# SCH_Hand_2024-01-24.net
KiCad netlist of a schematic drawn in EasyEDA
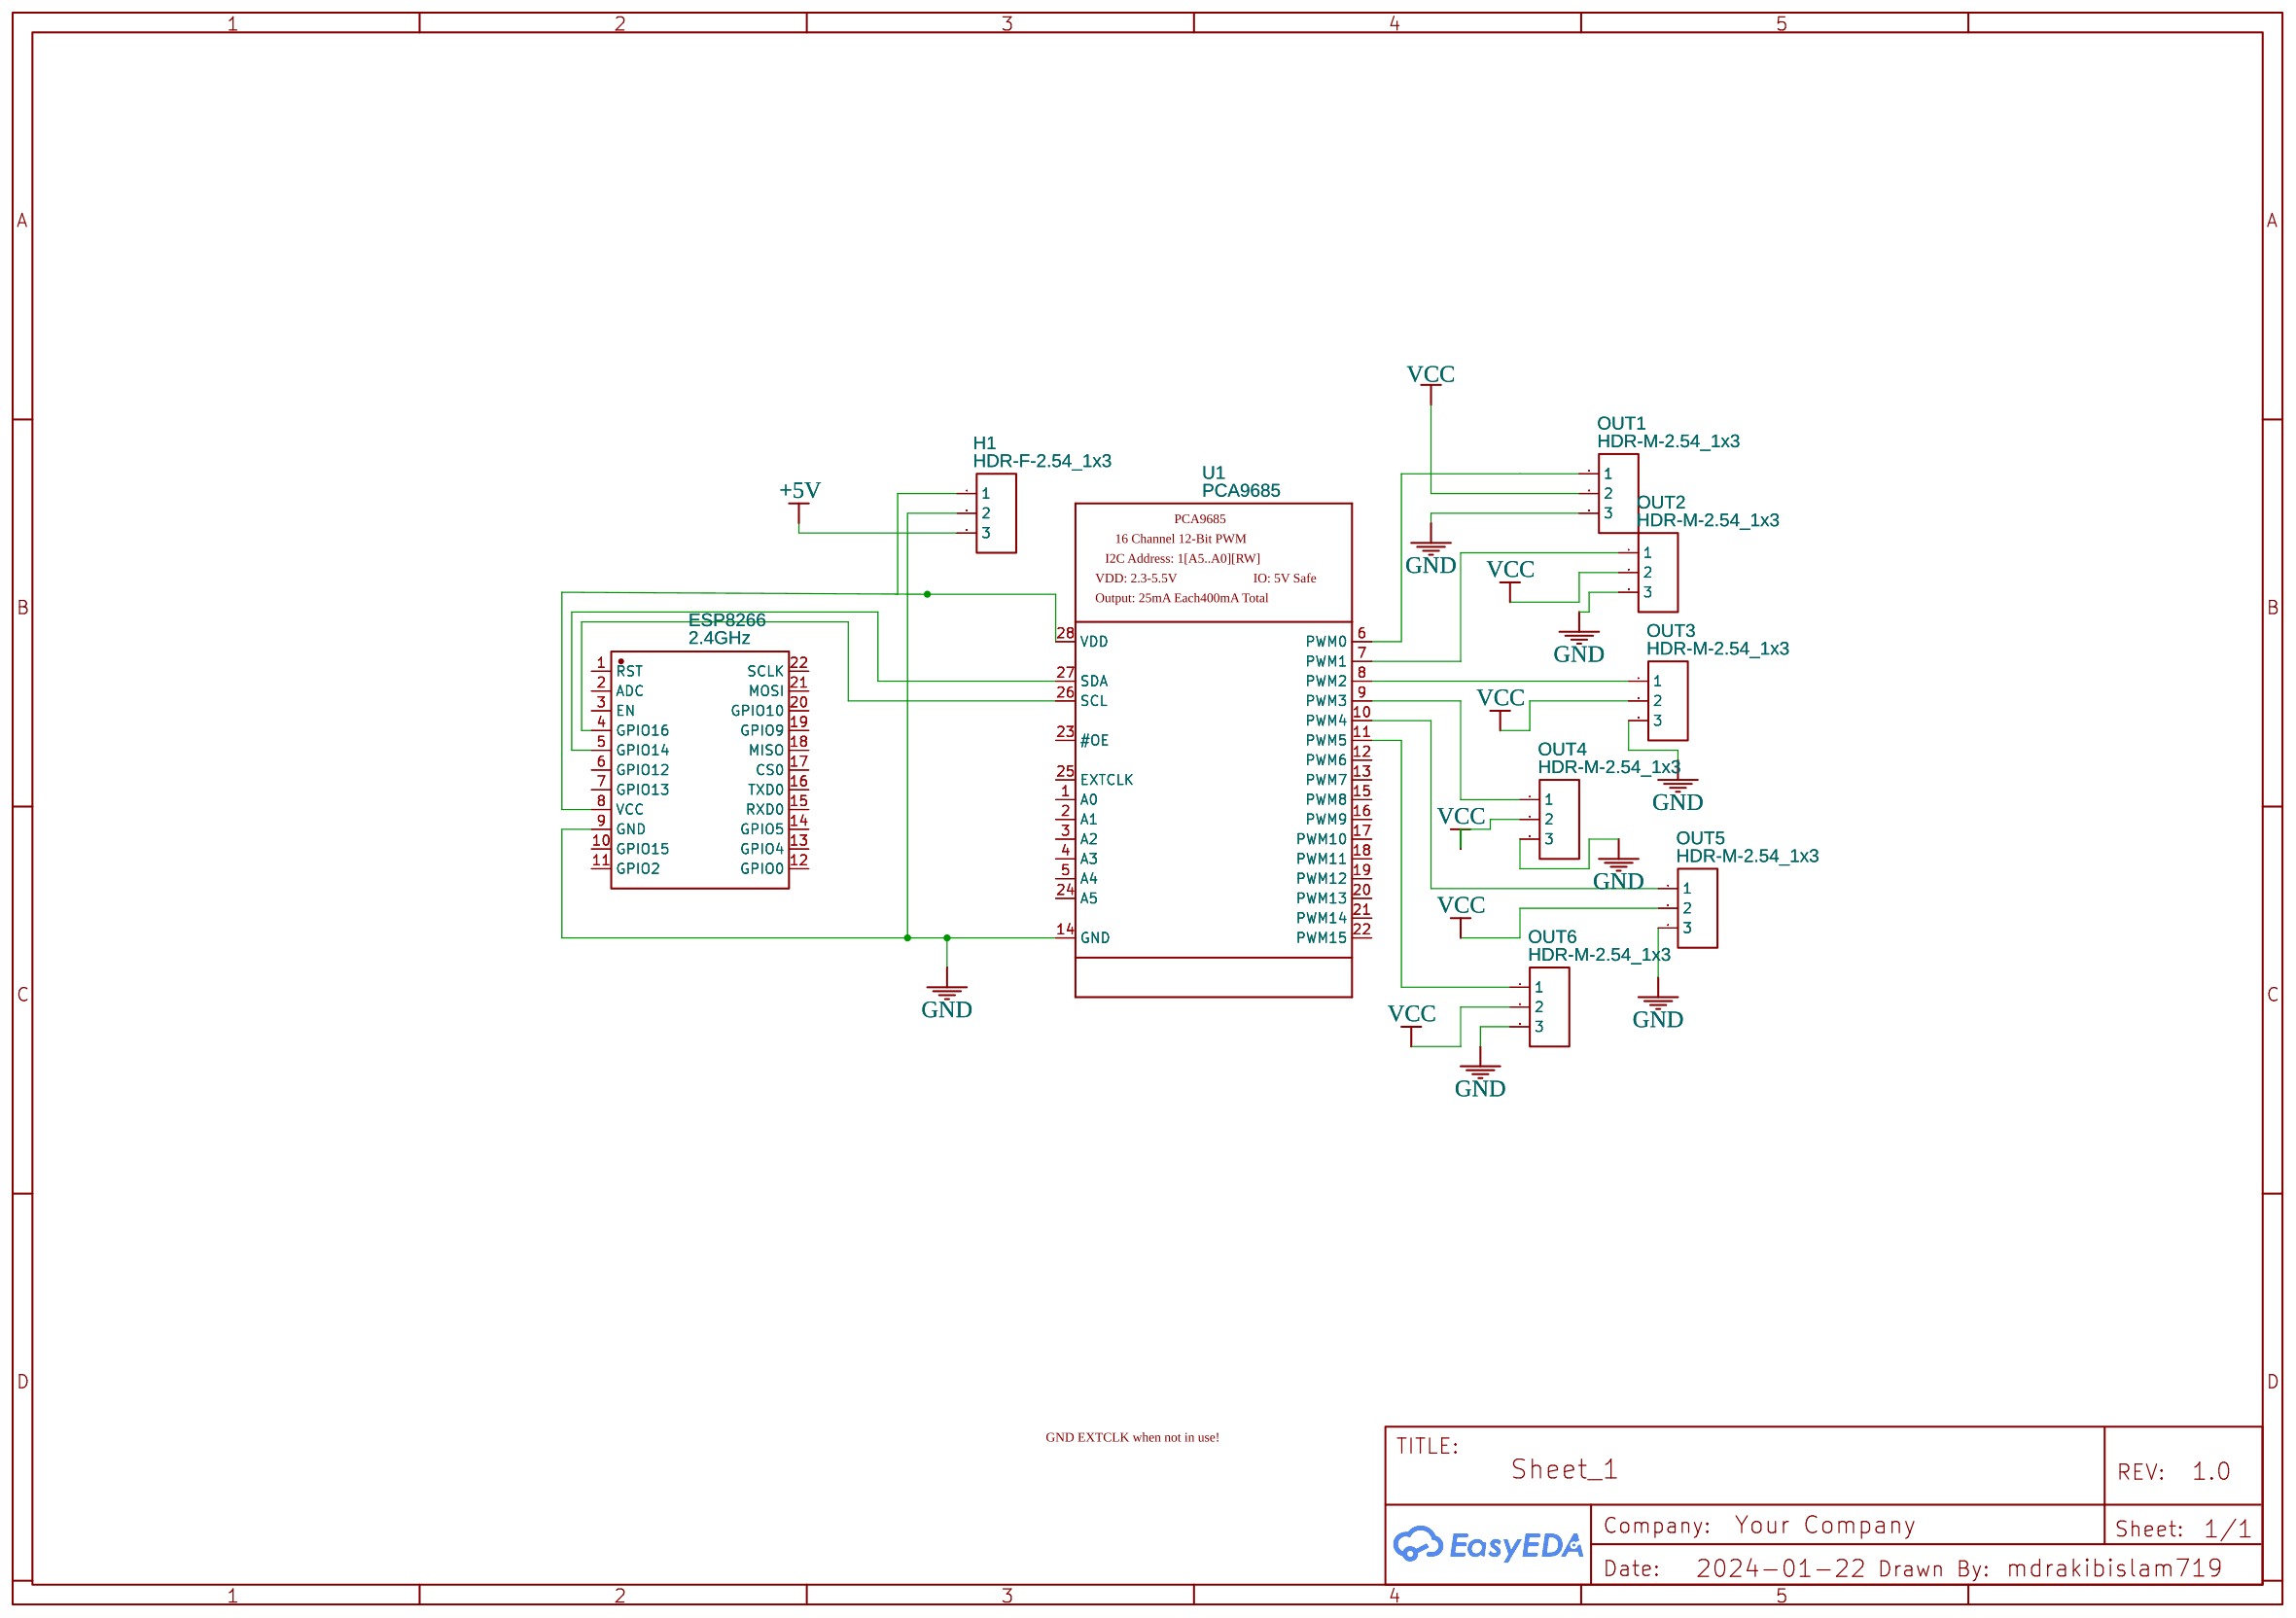
[diagram p0: schematic sheet]

(export (version "E")
  (design (tool "Eeschema 10.0.6"))
  (components
    (comp (ref "ESP8266")
      (value "2.4GHz")
      (fields
        (field (name "Manufacturer Part") "ESP-12F(ESP8266MOD)")
        (field (name "Manufacturer") "Ai-Thinker(安信可)")
      )
      (libsource (lib "") (part "ESP-12F(ESP8266MOD)"))
    )
    (comp (ref "H1") (value "HDR-F-2.54_1x3") (libsource (lib "") (part "HDR-F-2.54_1x3")))
    (comp (ref "OUT1") (value "HDR-M-2.54_1x3") (libsource (lib "") (part "HDR-M-2.54_1x3")))
    (comp (ref "OUT2") (value "HDR-M-2.54_1x3") (libsource (lib "") (part "HDR-M-2.54_1x3")))
    (comp (ref "OUT3") (value "HDR-M-2.54_1x3") (libsource (lib "") (part "HDR-M-2.54_1x3")))
    (comp (ref "OUT4") (value "HDR-M-2.54_1x3") (libsource (lib "") (part "HDR-M-2.54_1x3")))
    (comp (ref "OUT5") (value "HDR-M-2.54_1x3") (libsource (lib "") (part "HDR-M-2.54_1x3")))
    (comp (ref "OUT6") (value "HDR-M-2.54_1x3") (libsource (lib "") (part "HDR-M-2.54_1x3")))
    (comp (ref "U1") (value "PCA9685") (libsource (lib "") (part "PCA9685")))
  )
  (nets
    (net (code "1") (name "+5V") (class "Default")
      (node (ref "H1") (pin "3") (pinfunction "3_3") (pintype "input"))
    )
    (net (code "2") (name "GND") (class "Default")
      (node (ref "ESP8266") (pin "9") (pinfunction "GND_9") (pintype "unspecified"))
      (node (ref "H1") (pin "2") (pinfunction "2_2") (pintype "input"))
      (node (ref "OUT1") (pin "3") (pinfunction "3_3") (pintype "input"))
      (node (ref "OUT2") (pin "3") (pinfunction "3_3") (pintype "input"))
      (node (ref "OUT3") (pin "3") (pinfunction "3_3") (pintype "input"))
      (node (ref "OUT4") (pin "3") (pinfunction "3_3") (pintype "input"))
      (node (ref "OUT5") (pin "3") (pinfunction "3_3") (pintype "input"))
      (node (ref "OUT6") (pin "3") (pinfunction "3_3") (pintype "input"))
      (node (ref "U1") (pin "14") (pinfunction "GND_14") (pintype "passive"))
    )
    (net (code "3") (name "Net-(ESP8266-GPIO14)") (class "Default")
      (node (ref "ESP8266") (pin "5") (pinfunction "GPIO14_5") (pintype "unspecified"))
      (node (ref "U1") (pin "27") (pinfunction "SDA_27") (pintype "unspecified"))
    )
    (net (code "4") (name "Net-(ESP8266-GPIO16)") (class "Default")
      (node (ref "ESP8266") (pin "4") (pinfunction "GPIO16_4") (pintype "unspecified"))
      (node (ref "U1") (pin "26") (pinfunction "SCL_26") (pintype "unspecified"))
    )
    (net (code "5") (name "Net-(ESP8266-VCC)") (class "Default")
      (node (ref "ESP8266") (pin "8") (pinfunction "VCC_8") (pintype "unspecified"))
      (node (ref "U1") (pin "28") (pinfunction "VDD_28") (pintype "passive"))
    )
    (net (code "6") (name "Net-(U1-PWM0)") (class "Default")
      (node (ref "OUT1") (pin "1") (pinfunction "1_1") (pintype "input"))
      (node (ref "U1") (pin "6") (pinfunction "PWM0_6") (pintype "output"))
    )
    (net (code "7") (name "Net-(U1-PWM1)") (class "Default")
      (node (ref "OUT2") (pin "1") (pinfunction "1_1") (pintype "input"))
      (node (ref "U1") (pin "7") (pinfunction "PWM1_7") (pintype "output"))
    )
    (net (code "8") (name "Net-(U1-PWM2)") (class "Default")
      (node (ref "OUT3") (pin "1") (pinfunction "1_1") (pintype "input"))
      (node (ref "U1") (pin "8") (pinfunction "PWM2_8") (pintype "output"))
    )
    (net (code "9") (name "Net-(U1-PWM3)") (class "Default")
      (node (ref "OUT4") (pin "1") (pinfunction "1_1") (pintype "input"))
      (node (ref "U1") (pin "9") (pinfunction "PWM3_9") (pintype "output"))
    )
    (net (code "10") (name "Net-(U1-PWM4)") (class "Default")
      (node (ref "OUT5") (pin "1") (pinfunction "1_1") (pintype "input"))
      (node (ref "U1") (pin "10") (pinfunction "PWM4_10") (pintype "output"))
    )
    (net (code "11") (name "Net-(U1-PWM5)") (class "Default")
      (node (ref "OUT6") (pin "1") (pinfunction "1_1") (pintype "input"))
      (node (ref "U1") (pin "11") (pinfunction "PWM5_11") (pintype "output"))
    )
    (net (code "12") (name "VCC") (class "Default")
      (node (ref "OUT1") (pin "2") (pinfunction "2_2") (pintype "input"))
      (node (ref "OUT2") (pin "2") (pinfunction "2_2") (pintype "input"))
      (node (ref "OUT3") (pin "2") (pinfunction "2_2") (pintype "input"))
      (node (ref "OUT4") (pin "2") (pinfunction "2_2") (pintype "input"))
      (node (ref "OUT5") (pin "2") (pinfunction "2_2") (pintype "input"))
      (node (ref "OUT6") (pin "2") (pinfunction "2_2") (pintype "input"))
    )
    (net (code "13") (name "unconnected-(ESP8266-ADC-Pad2)") (class "Default")
      (node (ref "ESP8266") (pin "2") (pinfunction "ADC_2") (pintype "unspecified"))
    )
    (net (code "14") (name "unconnected-(ESP8266-CS0-Pad17)") (class "Default")
      (node (ref "ESP8266") (pin "17") (pinfunction "CS0_17") (pintype "unspecified"))
    )
    (net (code "15") (name "unconnected-(ESP8266-EN-Pad3)") (class "Default")
      (node (ref "ESP8266") (pin "3") (pinfunction "EN_3") (pintype "unspecified"))
    )
    (net (code "16") (name "unconnected-(ESP8266-GPIO0-Pad12)") (class "Default")
      (node (ref "ESP8266") (pin "12") (pinfunction "GPIO0_12") (pintype "unspecified"))
    )
    (net (code "17") (name "unconnected-(ESP8266-GPIO2-Pad11)") (class "Default")
      (node (ref "ESP8266") (pin "11") (pinfunction "GPIO2_11") (pintype "unspecified"))
    )
    (net (code "18") (name "unconnected-(ESP8266-GPIO4-Pad13)") (class "Default")
      (node (ref "ESP8266") (pin "13") (pinfunction "GPIO4_13") (pintype "unspecified"))
    )
    (net (code "19") (name "unconnected-(ESP8266-GPIO5-Pad14)") (class "Default")
      (node (ref "ESP8266") (pin "14") (pinfunction "GPIO5_14") (pintype "unspecified"))
    )
    (net (code "20") (name "unconnected-(ESP8266-GPIO9-Pad19)") (class "Default")
      (node (ref "ESP8266") (pin "19") (pinfunction "GPIO9_19") (pintype "unspecified"))
    )
    (net (code "21") (name "unconnected-(ESP8266-GPIO10-Pad20)") (class "Default")
      (node (ref "ESP8266") (pin "20") (pinfunction "GPIO10_20") (pintype "unspecified"))
    )
    (net (code "22") (name "unconnected-(ESP8266-GPIO12-Pad6)") (class "Default")
      (node (ref "ESP8266") (pin "6") (pinfunction "GPIO12_6") (pintype "unspecified"))
    )
    (net (code "23") (name "unconnected-(ESP8266-GPIO13-Pad7)") (class "Default")
      (node (ref "ESP8266") (pin "7") (pinfunction "GPIO13_7") (pintype "unspecified"))
    )
    (net (code "24") (name "unconnected-(ESP8266-GPIO15-Pad10)") (class "Default")
      (node (ref "ESP8266") (pin "10") (pinfunction "GPIO15_10") (pintype "unspecified"))
    )
    (net (code "25") (name "unconnected-(ESP8266-MISO-Pad18)") (class "Default")
      (node (ref "ESP8266") (pin "18") (pinfunction "MISO_18") (pintype "unspecified"))
    )
    (net (code "26") (name "unconnected-(ESP8266-MOSI-Pad21)") (class "Default")
      (node (ref "ESP8266") (pin "21") (pinfunction "MOSI_21") (pintype "unspecified"))
    )
    (net (code "27") (name "unconnected-(ESP8266-RST-Pad1)") (class "Default")
      (node (ref "ESP8266") (pin "1") (pinfunction "RST_1") (pintype "unspecified"))
    )
    (net (code "28") (name "unconnected-(ESP8266-RXD0-Pad15)") (class "Default")
      (node (ref "ESP8266") (pin "15") (pinfunction "RXD0_15") (pintype "unspecified"))
    )
    (net (code "29") (name "unconnected-(ESP8266-SCLK-Pad22)") (class "Default")
      (node (ref "ESP8266") (pin "22") (pinfunction "SCLK_22") (pintype "unspecified"))
    )
    (net (code "30") (name "unconnected-(ESP8266-TXD0-Pad16)") (class "Default")
      (node (ref "ESP8266") (pin "16") (pinfunction "TXD0_16") (pintype "unspecified"))
    )
    (net (code "31") (name "unconnected-(H1-Pad1)") (class "Default")
      (node (ref "H1") (pin "1") (pinfunction "1_1") (pintype "input"))
    )
    (net (code "32") (name "unconnected-(U1-#OE-Pad23)") (class "Default")
      (node (ref "U1") (pin "23") (pinfunction "#OE_23") (pintype "input"))
    )
    (net (code "33") (name "unconnected-(U1-A0-Pad1)") (class "Default")
      (node (ref "U1") (pin "1") (pinfunction "A0_1") (pintype "unspecified"))
    )
    (net (code "34") (name "unconnected-(U1-A1-Pad2)") (class "Default")
      (node (ref "U1") (pin "2") (pinfunction "A1_2") (pintype "unspecified"))
    )
    (net (code "35") (name "unconnected-(U1-A2-Pad3)") (class "Default")
      (node (ref "U1") (pin "3") (pinfunction "A2_3") (pintype "unspecified"))
    )
    (net (code "36") (name "unconnected-(U1-A3-Pad4)") (class "Default")
      (node (ref "U1") (pin "4") (pinfunction "A3_4") (pintype "unspecified"))
    )
    (net (code "37") (name "unconnected-(U1-A4-Pad5)") (class "Default")
      (node (ref "U1") (pin "5") (pinfunction "A4_5") (pintype "unspecified"))
    )
    (net (code "38") (name "unconnected-(U1-A5-Pad24)") (class "Default")
      (node (ref "U1") (pin "24") (pinfunction "A5_24") (pintype "unspecified"))
    )
    (net (code "39") (name "unconnected-(U1-EXTCLK-Pad25)") (class "Default")
      (node (ref "U1") (pin "25") (pinfunction "EXTCLK_25") (pintype "input"))
    )
    (net (code "40") (name "unconnected-(U1-PWM6-Pad12)") (class "Default")
      (node (ref "U1") (pin "12") (pinfunction "PWM6_12") (pintype "output"))
    )
    (net (code "41") (name "unconnected-(U1-PWM7-Pad13)") (class "Default")
      (node (ref "U1") (pin "13") (pinfunction "PWM7_13") (pintype "output"))
    )
    (net (code "42") (name "unconnected-(U1-PWM8-Pad15)") (class "Default")
      (node (ref "U1") (pin "15") (pinfunction "PWM8_15") (pintype "output"))
    )
    (net (code "43") (name "unconnected-(U1-PWM9-Pad16)") (class "Default")
      (node (ref "U1") (pin "16") (pinfunction "PWM9_16") (pintype "output"))
    )
    (net (code "44") (name "unconnected-(U1-PWM10-Pad17)") (class "Default")
      (node (ref "U1") (pin "17") (pinfunction "PWM10_17") (pintype "output"))
    )
    (net (code "45") (name "unconnected-(U1-PWM11-Pad18)") (class "Default")
      (node (ref "U1") (pin "18") (pinfunction "PWM11_18") (pintype "output"))
    )
    (net (code "46") (name "unconnected-(U1-PWM12-Pad19)") (class "Default")
      (node (ref "U1") (pin "19") (pinfunction "PWM12_19") (pintype "output"))
    )
    (net (code "47") (name "unconnected-(U1-PWM13-Pad20)") (class "Default")
      (node (ref "U1") (pin "20") (pinfunction "PWM13_20") (pintype "output"))
    )
    (net (code "48") (name "unconnected-(U1-PWM14-Pad21)") (class "Default")
      (node (ref "U1") (pin "21") (pinfunction "PWM14_21") (pintype "output"))
    )
    (net (code "49") (name "unconnected-(U1-PWM15-Pad22)") (class "Default")
      (node (ref "U1") (pin "22") (pinfunction "PWM15_22") (pintype "output"))
    )
  )
)
